# DashDialV3.net
KiCad netlist of a schematic drawn in EAGLE
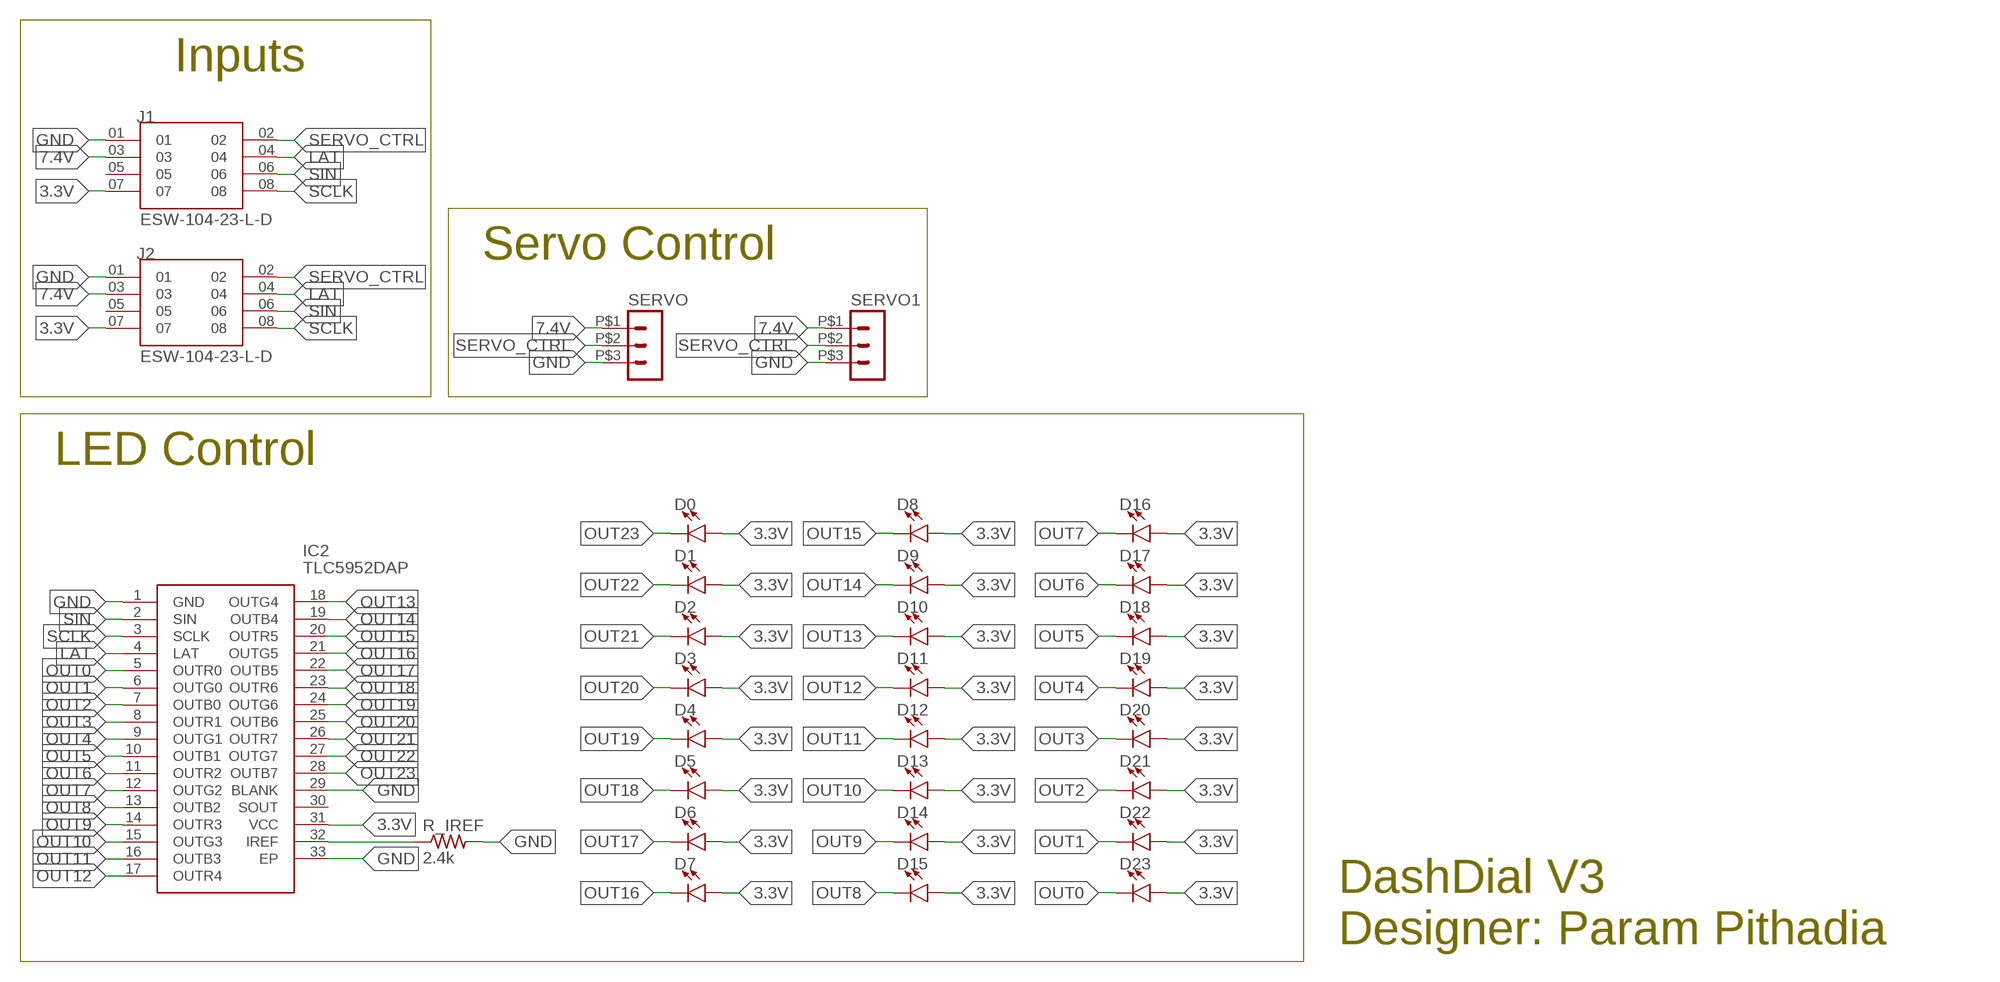
[diagram p0: schematic, sheet 1]

(export (version "E")
  (design (tool "Eeschema 10.0.6"))
  (components
    (comp (ref "D0")
      (value "LED3MM")
      (footprint "eagle-import:LED_3MM")
      (libsource (lib "eagle-import") (part "LED3MM"))
    )
    (comp (ref "D1")
      (value "LED3MM")
      (footprint "eagle-import:LED_3MM")
      (libsource (lib "eagle-import") (part "LED3MM"))
    )
    (comp (ref "D2")
      (value "LED3MM")
      (footprint "eagle-import:LED_3MM")
      (libsource (lib "eagle-import") (part "LED3MM"))
    )
    (comp (ref "D3")
      (value "LED3MM")
      (footprint "eagle-import:LED_3MM")
      (libsource (lib "eagle-import") (part "LED3MM"))
    )
    (comp (ref "D4")
      (value "LED3MM")
      (footprint "eagle-import:LED_3MM")
      (libsource (lib "eagle-import") (part "LED3MM"))
    )
    (comp (ref "D5")
      (value "LED3MM")
      (footprint "eagle-import:LED_3MM")
      (libsource (lib "eagle-import") (part "LED3MM"))
    )
    (comp (ref "D6")
      (value "LED3MM")
      (footprint "eagle-import:LED_3MM")
      (libsource (lib "eagle-import") (part "LED3MM"))
    )
    (comp (ref "D7")
      (value "LED3MM")
      (footprint "eagle-import:LED_3MM")
      (libsource (lib "eagle-import") (part "LED3MM"))
    )
    (comp (ref "D8")
      (value "LED3MM")
      (footprint "eagle-import:LED_3MM")
      (libsource (lib "eagle-import") (part "LED3MM"))
    )
    (comp (ref "D9")
      (value "LED3MM")
      (footprint "eagle-import:LED_3MM")
      (libsource (lib "eagle-import") (part "LED3MM"))
    )
    (comp (ref "D10")
      (value "LED3MM")
      (footprint "eagle-import:LED_3MM")
      (libsource (lib "eagle-import") (part "LED3MM"))
    )
    (comp (ref "D11")
      (value "LED3MM")
      (footprint "eagle-import:LED_3MM")
      (libsource (lib "eagle-import") (part "LED3MM"))
    )
    (comp (ref "D12")
      (value "LED3MM")
      (footprint "eagle-import:LED_3MM")
      (libsource (lib "eagle-import") (part "LED3MM"))
    )
    (comp (ref "D13")
      (value "LED3MM")
      (footprint "eagle-import:LED_3MM")
      (libsource (lib "eagle-import") (part "LED3MM"))
    )
    (comp (ref "D14")
      (value "LED3MM")
      (footprint "eagle-import:LED_3MM")
      (libsource (lib "eagle-import") (part "LED3MM"))
    )
    (comp (ref "D15")
      (value "LED3MM")
      (footprint "eagle-import:LED_3MM")
      (libsource (lib "eagle-import") (part "LED3MM"))
    )
    (comp (ref "D16")
      (value "LED3MM")
      (footprint "eagle-import:LED_3MM")
      (libsource (lib "eagle-import") (part "LED3MM"))
    )
    (comp (ref "D17")
      (value "LED3MM")
      (footprint "eagle-import:LED_3MM")
      (libsource (lib "eagle-import") (part "LED3MM"))
    )
    (comp (ref "D18")
      (value "LED3MM")
      (footprint "eagle-import:LED_3MM")
      (libsource (lib "eagle-import") (part "LED3MM"))
    )
    (comp (ref "D19")
      (value "LED3MM")
      (footprint "eagle-import:LED_3MM")
      (libsource (lib "eagle-import") (part "LED3MM"))
    )
    (comp (ref "D20")
      (value "LED3MM")
      (footprint "eagle-import:LED_3MM")
      (libsource (lib "eagle-import") (part "LED3MM"))
    )
    (comp (ref "D21")
      (value "LED3MM")
      (footprint "eagle-import:LED_3MM")
      (libsource (lib "eagle-import") (part "LED3MM"))
    )
    (comp (ref "D22")
      (value "LED3MM")
      (footprint "eagle-import:LED_3MM")
      (libsource (lib "eagle-import") (part "LED3MM"))
    )
    (comp (ref "D23")
      (value "LED3MM")
      (footprint "eagle-import:LED_3MM")
      (libsource (lib "eagle-import") (part "LED3MM"))
    )
    (comp (ref "IC2")
      (value "TLC5952DAP")
      (footprint "eagle-import:SOP65P810X120-33N")
      (fields (field (name "MOUSER_PART_NUMBER") "595-TLC5952DAP"))
      (libsource (lib "eagle-import") (part "TLC5952DAP"))
    )
    (comp (ref "J1")
      (value "ESW-104-23-L-D")
      (footprint "eagle-import:SAMTEC_ESW-104-23-L-D")
      (fields (field (name "MANUFACTURER") "Samtec Inc."))
      (libsource (lib "eagle-import") (part "ESW-104-23-L-D"))
    )
    (comp (ref "J2")
      (value "ESW-104-23-L-D")
      (footprint "eagle-import:SAMTEC_ESW-104-23-L-D")
      (fields (field (name "MANUFACTURER") "Samtec Inc."))
      (libsource (lib "eagle-import") (part "ESW-104-23-L-D"))
    )
    (comp (ref "R_IREF")
      (value "2.4k")
      (footprint "eagle-import:R0603")
      (libsource (lib "eagle-import") (part "RES_SMDR0603"))
    )
    (comp (ref "SERVO")
      (value "HEADER_POS3_43650-0300")
      (footprint "eagle-import:43650-0300")
      (libsource (lib "eagle-import") (part "HEADER_POS3_?43650-0300"))
    )
    (comp (ref "SERVO1")
      (value "HEADER_POS3_43650-0300")
      (footprint "eagle-import:43650-0300")
      (libsource (lib "eagle-import") (part "HEADER_POS3_?43650-0300"))
    )
  )
  (nets
    (net (code "1") (name "3.3V") (class "Default")
      (node (ref "D0") (pin "A") (pinfunction "A_A") (pintype "passive"))
      (node (ref "D1") (pin "A") (pinfunction "A_A") (pintype "passive"))
      (node (ref "D10") (pin "A") (pinfunction "A_A") (pintype "passive"))
      (node (ref "D11") (pin "A") (pinfunction "A_A") (pintype "passive"))
      (node (ref "D12") (pin "A") (pinfunction "A_A") (pintype "passive"))
      (node (ref "D13") (pin "A") (pinfunction "A_A") (pintype "passive"))
      (node (ref "D14") (pin "A") (pinfunction "A_A") (pintype "passive"))
      (node (ref "D15") (pin "A") (pinfunction "A_A") (pintype "passive"))
      (node (ref "D16") (pin "A") (pinfunction "A_A") (pintype "passive"))
      (node (ref "D17") (pin "A") (pinfunction "A_A") (pintype "passive"))
      (node (ref "D18") (pin "A") (pinfunction "A_A") (pintype "passive"))
      (node (ref "D19") (pin "A") (pinfunction "A_A") (pintype "passive"))
      (node (ref "D2") (pin "A") (pinfunction "A_A") (pintype "passive"))
      (node (ref "D20") (pin "A") (pinfunction "A_A") (pintype "passive"))
      (node (ref "D21") (pin "A") (pinfunction "A_A") (pintype "passive"))
      (node (ref "D22") (pin "A") (pinfunction "A_A") (pintype "passive"))
      (node (ref "D23") (pin "A") (pinfunction "A_A") (pintype "passive"))
      (node (ref "D3") (pin "A") (pinfunction "A_A") (pintype "passive"))
      (node (ref "D4") (pin "A") (pinfunction "A_A") (pintype "passive"))
      (node (ref "D5") (pin "A") (pinfunction "A_A") (pintype "passive"))
      (node (ref "D6") (pin "A") (pinfunction "A_A") (pintype "passive"))
      (node (ref "D7") (pin "A") (pinfunction "A_A") (pintype "passive"))
      (node (ref "D8") (pin "A") (pinfunction "A_A") (pintype "passive"))
      (node (ref "D9") (pin "A") (pinfunction "A_A") (pintype "passive"))
      (node (ref "IC2") (pin "31") (pinfunction "VCC_31") (pintype "bidirectional"))
      (node (ref "J1") (pin "07") (pinfunction "07_07") (pintype "passive"))
      (node (ref "J2") (pin "07") (pinfunction "07_07") (pintype "passive"))
    )
    (net (code "2") (name "7.4V") (class "Default")
      (node (ref "J1") (pin "03") (pinfunction "03_03") (pintype "passive"))
      (node (ref "J2") (pin "03") (pinfunction "03_03") (pintype "passive"))
      (node (ref "SERVO") (pin "P$1") (pinfunction "1_P$1") (pintype "passive"))
      (node (ref "SERVO1") (pin "P$1") (pinfunction "1_P$1") (pintype "passive"))
    )
    (net (code "3") (name "GND") (class "Default")
      (node (ref "IC2") (pin "1") (pinfunction "GND_1") (pintype "bidirectional"))
      (node (ref "IC2") (pin "29") (pinfunction "BLANK_29") (pintype "bidirectional"))
      (node (ref "IC2") (pin "33") (pinfunction "EP_33") (pintype "bidirectional"))
      (node (ref "J1") (pin "01") (pinfunction "01_01") (pintype "passive"))
      (node (ref "J2") (pin "01") (pinfunction "01_01") (pintype "passive"))
      (node (ref "R_IREF") (pin "2") (pinfunction "2_2") (pintype "passive"))
      (node (ref "SERVO") (pin "P$3") (pinfunction "3_P$3") (pintype "passive"))
      (node (ref "SERVO1") (pin "P$3") (pinfunction "3_P$3") (pintype "passive"))
    )
    (net (code "4") (name "LAT") (class "Default")
      (node (ref "IC2") (pin "4") (pinfunction "LAT_4") (pintype "bidirectional"))
      (node (ref "J1") (pin "04") (pinfunction "04_04") (pintype "passive"))
      (node (ref "J2") (pin "04") (pinfunction "04_04") (pintype "passive"))
    )
    (net (code "5") (name "Net-(IC2-IREF)") (class "Default")
      (node (ref "IC2") (pin "32") (pinfunction "IREF_32") (pintype "bidirectional"))
      (node (ref "R_IREF") (pin "1") (pinfunction "1_1") (pintype "passive"))
    )
    (net (code "6") (name "OUT0") (class "Default")
      (node (ref "D23") (pin "K") (pinfunction "C_K") (pintype "passive"))
      (node (ref "IC2") (pin "5") (pinfunction "OUTR0_5") (pintype "bidirectional"))
    )
    (net (code "7") (name "OUT1") (class "Default")
      (node (ref "D22") (pin "K") (pinfunction "C_K") (pintype "passive"))
      (node (ref "IC2") (pin "6") (pinfunction "OUTG0_6") (pintype "bidirectional"))
    )
    (net (code "8") (name "OUT2") (class "Default")
      (node (ref "D21") (pin "K") (pinfunction "C_K") (pintype "passive"))
      (node (ref "IC2") (pin "7") (pinfunction "OUTB0_7") (pintype "bidirectional"))
    )
    (net (code "9") (name "OUT3") (class "Default")
      (node (ref "D20") (pin "K") (pinfunction "C_K") (pintype "passive"))
      (node (ref "IC2") (pin "8") (pinfunction "OUTR1_8") (pintype "bidirectional"))
    )
    (net (code "10") (name "OUT4") (class "Default")
      (node (ref "D19") (pin "K") (pinfunction "C_K") (pintype "passive"))
      (node (ref "IC2") (pin "9") (pinfunction "OUTG1_9") (pintype "bidirectional"))
    )
    (net (code "11") (name "OUT5") (class "Default")
      (node (ref "D18") (pin "K") (pinfunction "C_K") (pintype "passive"))
      (node (ref "IC2") (pin "10") (pinfunction "OUTB1_10") (pintype "bidirectional"))
    )
    (net (code "12") (name "OUT6") (class "Default")
      (node (ref "D17") (pin "K") (pinfunction "C_K") (pintype "passive"))
      (node (ref "IC2") (pin "11") (pinfunction "OUTR2_11") (pintype "bidirectional"))
    )
    (net (code "13") (name "OUT7") (class "Default")
      (node (ref "D16") (pin "K") (pinfunction "C_K") (pintype "passive"))
      (node (ref "IC2") (pin "12") (pinfunction "OUTG2_12") (pintype "bidirectional"))
    )
    (net (code "14") (name "OUT8") (class "Default")
      (node (ref "D15") (pin "K") (pinfunction "C_K") (pintype "passive"))
      (node (ref "IC2") (pin "13") (pinfunction "OUTB2_13") (pintype "bidirectional"))
    )
    (net (code "15") (name "OUT9") (class "Default")
      (node (ref "D14") (pin "K") (pinfunction "C_K") (pintype "passive"))
      (node (ref "IC2") (pin "14") (pinfunction "OUTR3_14") (pintype "bidirectional"))
    )
    (net (code "16") (name "OUT10") (class "Default")
      (node (ref "D13") (pin "K") (pinfunction "C_K") (pintype "passive"))
      (node (ref "IC2") (pin "15") (pinfunction "OUTG3_15") (pintype "bidirectional"))
    )
    (net (code "17") (name "OUT11") (class "Default")
      (node (ref "D12") (pin "K") (pinfunction "C_K") (pintype "passive"))
      (node (ref "IC2") (pin "16") (pinfunction "OUTB3_16") (pintype "bidirectional"))
    )
    (net (code "18") (name "OUT12") (class "Default")
      (node (ref "D11") (pin "K") (pinfunction "C_K") (pintype "passive"))
      (node (ref "IC2") (pin "17") (pinfunction "OUTR4_17") (pintype "bidirectional"))
    )
    (net (code "19") (name "OUT13") (class "Default")
      (node (ref "D10") (pin "K") (pinfunction "C_K") (pintype "passive"))
      (node (ref "IC2") (pin "18") (pinfunction "OUTG4_18") (pintype "bidirectional"))
    )
    (net (code "20") (name "OUT14") (class "Default")
      (node (ref "D9") (pin "K") (pinfunction "C_K") (pintype "passive"))
      (node (ref "IC2") (pin "19") (pinfunction "OUTB4_19") (pintype "bidirectional"))
    )
    (net (code "21") (name "OUT15") (class "Default")
      (node (ref "D8") (pin "K") (pinfunction "C_K") (pintype "passive"))
      (node (ref "IC2") (pin "20") (pinfunction "OUTR5_20") (pintype "bidirectional"))
    )
    (net (code "22") (name "OUT16") (class "Default")
      (node (ref "D7") (pin "K") (pinfunction "C_K") (pintype "passive"))
      (node (ref "IC2") (pin "21") (pinfunction "OUTG5_21") (pintype "bidirectional"))
    )
    (net (code "23") (name "OUT17") (class "Default")
      (node (ref "D6") (pin "K") (pinfunction "C_K") (pintype "passive"))
      (node (ref "IC2") (pin "22") (pinfunction "OUTB5_22") (pintype "bidirectional"))
    )
    (net (code "24") (name "OUT18") (class "Default")
      (node (ref "D5") (pin "K") (pinfunction "C_K") (pintype "passive"))
      (node (ref "IC2") (pin "23") (pinfunction "OUTR6_23") (pintype "bidirectional"))
    )
    (net (code "25") (name "OUT19") (class "Default")
      (node (ref "D4") (pin "K") (pinfunction "C_K") (pintype "passive"))
      (node (ref "IC2") (pin "24") (pinfunction "OUTG6_24") (pintype "bidirectional"))
    )
    (net (code "26") (name "OUT20") (class "Default")
      (node (ref "D3") (pin "K") (pinfunction "C_K") (pintype "passive"))
      (node (ref "IC2") (pin "25") (pinfunction "OUTB6_25") (pintype "bidirectional"))
    )
    (net (code "27") (name "OUT21") (class "Default")
      (node (ref "D2") (pin "K") (pinfunction "C_K") (pintype "passive"))
      (node (ref "IC2") (pin "26") (pinfunction "OUTR7_26") (pintype "bidirectional"))
    )
    (net (code "28") (name "OUT22") (class "Default")
      (node (ref "D1") (pin "K") (pinfunction "C_K") (pintype "passive"))
      (node (ref "IC2") (pin "27") (pinfunction "OUTG7_27") (pintype "bidirectional"))
    )
    (net (code "29") (name "OUT23") (class "Default")
      (node (ref "D0") (pin "K") (pinfunction "C_K") (pintype "passive"))
      (node (ref "IC2") (pin "28") (pinfunction "OUTB7_28") (pintype "bidirectional"))
    )
    (net (code "30") (name "SCLK") (class "Default")
      (node (ref "IC2") (pin "3") (pinfunction "SCLK_3") (pintype "bidirectional"))
      (node (ref "J1") (pin "08") (pinfunction "08_08") (pintype "passive"))
      (node (ref "J2") (pin "08") (pinfunction "08_08") (pintype "passive"))
    )
    (net (code "31") (name "SERVO_CTRL") (class "Default")
      (node (ref "J1") (pin "02") (pinfunction "02_02") (pintype "passive"))
      (node (ref "J2") (pin "02") (pinfunction "02_02") (pintype "passive"))
      (node (ref "SERVO") (pin "P$2") (pinfunction "2_P$2") (pintype "passive"))
      (node (ref "SERVO1") (pin "P$2") (pinfunction "2_P$2") (pintype "passive"))
    )
    (net (code "32") (name "SIN") (class "Default")
      (node (ref "IC2") (pin "2") (pinfunction "SIN_2") (pintype "bidirectional"))
      (node (ref "J1") (pin "06") (pinfunction "06_06") (pintype "passive"))
      (node (ref "J2") (pin "06") (pinfunction "06_06") (pintype "passive"))
    )
    (net (code "33") (name "unconnected-(IC2-SOUT-Pad30)") (class "Default")
      (node (ref "IC2") (pin "30") (pinfunction "SOUT_30") (pintype "bidirectional"))
    )
    (net (code "34") (name "unconnected-(J1-Pad05)") (class "Default")
      (node (ref "J1") (pin "05") (pinfunction "05_05") (pintype "passive"))
    )
    (net (code "35") (name "unconnected-(J2-Pad05)") (class "Default")
      (node (ref "J2") (pin "05") (pinfunction "05_05") (pintype "passive"))
    )
  )
)
